# vibration_sensor.net
KiCad netlist of a schematic drawn in Altium Designer
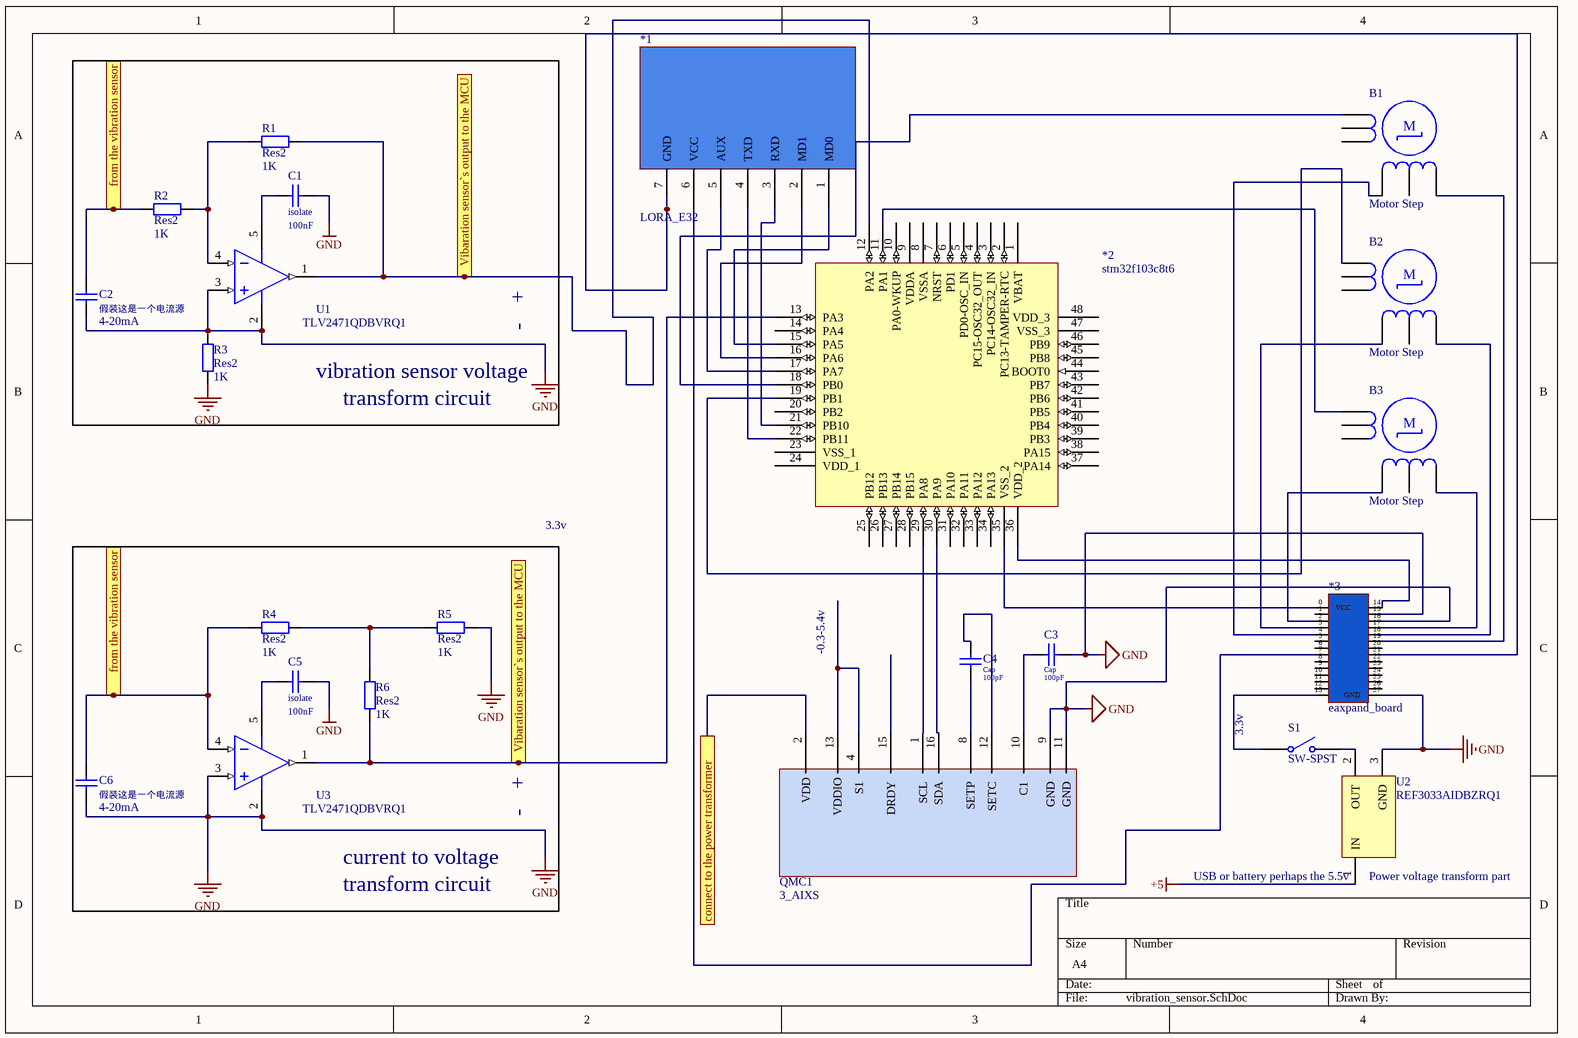
[diagram p0: vibration_sensor.SchDoc]

(export (version "E")
  (design (tool "Eeschema 10.0.6"))
  (components
    (comp (ref "*1")
      (value "LORA_E32")
      (footprint "LORA_AS62-T20")
      (description "EBYTE_USE_SEMTCH_CORE")
      (libsource (lib "lora") (part "LORA_E32"))
    )
    (comp (ref "*2") (value "stm32f103c8t6") (libsource (lib "stm32f103c8t6") (part "stm32f103c8t6")))
    (comp (ref "*3")
      (value "eaxpand_board")
      (footprint "expand_board")
      (libsource (lib "My_library") (part "eaxpand_board"))
    )
    (comp (ref "B1")
      (value "Motor Step")
      (footprint "DIP-6")
      (description "Motor Stepper")
      (fields (field (name "PUBLISHER") "Altium Limited"))
      (libsource (lib "Miscellaneous Devices") (part "Motor Step"))
    )
    (comp (ref "B2")
      (value "Motor Step")
      (footprint "DIP-6")
      (description "Motor Stepper")
      (fields (field (name "PUBLISHER") "Altium Limited"))
      (libsource (lib "Miscellaneous Devices") (part "Motor Step"))
    )
    (comp (ref "B3")
      (value "Motor Step")
      (footprint "DIP-6")
      (description "Motor Stepper")
      (fields (field (name "PUBLISHER") "Altium Limited"))
      (libsource (lib "Miscellaneous Devices") (part "Motor Step"))
    )
    (comp (ref "C1")
      (value "isolate")
      (footprint "RAD-0.3")
      (description "Capacitor")
      (fields (field (name "ALTIUM_VALUE") "100nF") (field (name "PUBLISHER") "Altium Limited"))
      (libsource (lib "Miscellaneous Devices") (part "Cap"))
    )
    (comp (ref "C2")
      (value "假装这是一个电流源")
      (footprint "RAD-0.3")
      (description "Capacitor")
      (fields (field (name "ALTIUM_VALUE") "4-20mA") (field (name "PUBLISHER") "Altium Limited"))
      (libsource (lib "Miscellaneous Devices") (part "Cap"))
    )
    (comp (ref "C3")
      (value "Cap")
      (footprint "RAD-0.3")
      (description "Capacitor")
      (fields (field (name "ALTIUM_VALUE") "100pF") (field (name "PUBLISHER") "Altium Limited"))
      (libsource (lib "Miscellaneous Devices") (part "Cap"))
    )
    (comp (ref "C4")
      (value "Cap")
      (footprint "RAD-0.3")
      (description "Capacitor")
      (fields (field (name "ALTIUM_VALUE") "100pF") (field (name "PUBLISHER") "Altium Limited"))
      (libsource (lib "Miscellaneous Devices") (part "Cap"))
    )
    (comp (ref "C5")
      (value "isolate")
      (footprint "RAD-0.3")
      (description "Capacitor")
      (fields (field (name "ALTIUM_VALUE") "100nF") (field (name "PUBLISHER") "Altium Limited"))
      (libsource (lib "Miscellaneous Devices") (part "Cap"))
    )
    (comp (ref "C6")
      (value "假装这是一个电流源")
      (footprint "RAD-0.3")
      (description "Capacitor")
      (fields (field (name "ALTIUM_VALUE") "4-20mA") (field (name "PUBLISHER") "Altium Limited"))
      (libsource (lib "Miscellaneous Devices") (part "Cap"))
    )
    (comp (ref "QMC1") (value "3_AIXS") (libsource (lib "QMC5883L") (part "QMC5883L")))
    (comp (ref "R1")
      (value "Res2")
      (footprint "AXIAL-0.4")
      (description "Resistor")
      (fields (field (name "ALTIUM_VALUE") "1K") (field (name "PUBLISHER") "Altium Limited"))
      (libsource (lib "") (part "Res2_2"))
    )
    (comp (ref "R2")
      (value "Res2")
      (footprint "AXIAL-0.4")
      (description "Resistor")
      (fields (field (name "ALTIUM_VALUE") "1K") (field (name "PUBLISHER") "Altium Limited"))
      (libsource (lib "Miscellaneous Devices") (part "Res2"))
    )
    (comp (ref "R3")
      (value "Res2")
      (footprint "AXIAL-0.4")
      (description "Resistor")
      (fields (field (name "ALTIUM_VALUE") "1K") (field (name "PUBLISHER") "Altium Limited"))
      (libsource (lib "") (part "Res2_1"))
    )
    (comp (ref "R4")
      (value "Res2")
      (footprint "AXIAL-0.4")
      (description "Resistor")
      (fields (field (name "ALTIUM_VALUE") "1K") (field (name "PUBLISHER") "Altium Limited"))
      (libsource (lib "") (part "Res2_2"))
    )
    (comp (ref "R5")
      (value "Res2")
      (footprint "AXIAL-0.4")
      (description "Resistor")
      (fields (field (name "ALTIUM_VALUE") "1K") (field (name "PUBLISHER") "Altium Limited"))
      (libsource (lib "Miscellaneous Devices") (part "Res2"))
    )
    (comp (ref "R6")
      (value "Res2")
      (footprint "AXIAL-0.4")
      (description "Resistor")
      (fields (field (name "ALTIUM_VALUE") "1K") (field (name "PUBLISHER") "Altium Limited"))
      (libsource (lib "") (part "Res2_1"))
    )
    (comp (ref "S1")
      (value "SW-SPST")
      (footprint "SPST-2")
      (description "Single-Pole, Single-Throw Switch")
      (fields (field (name "PUBLISHER") "Altium Limited"))
      (libsource (lib "Miscellaneous Devices") (part "SW-SPST"))
    )
    (comp (ref "U1")
      (value "TLV2471QDBVRQ1")
      (footprint "TI-DBV5_N")
      (fields (field (name "MANUFACTURER") "Texas Instruments"))
      (libsource (lib "TI Amplifiers and Linear Operational Amplifier Precision Amplifier Part Two") (part "TLV2471QDBVRQ1"))
    )
    (comp (ref "U2")
      (value "REF3033AIDBZRQ1")
      (footprint "TI-DBZ3_N")
      (fields (field (name "MANUFACTURER") "Texas Instruments"))
      (libsource (lib "TI Power Management Series Voltage Reference") (part "REF3033AIDBZRQ1"))
    )
    (comp (ref "U3")
      (value "TLV2471QDBVRQ1")
      (footprint "TI-DBV5_N")
      (fields (field (name "MANUFACTURER") "Texas Instruments"))
      (libsource (lib "TI Amplifiers and Linear Operational Amplifier Precision Amplifier Part Two") (part "TLV2471QDBVRQ1"))
    )
  )
  (nets
    (net (code "1") (name "+5") (class "Default")
      (node (ref "U2") (pin "1") (pinfunction "IN_1") (pintype "power_in"))
    )
    (net (code "2") (name "/Vibaration sensor`s output to the MCU") (class "Default")
      (node (ref "*2") (pin "12") (pinfunction "PA2_12") (pintype "bidirectional"))
      (node (ref "*2") (pin "13") (pinfunction "PA3_13") (pintype "bidirectional"))
      (node (ref "R1") (pin "1") (pinfunction "1_1") (pintype "passive"))
      (node (ref "R6") (pin "1") (pinfunction "1_1") (pintype "passive"))
      (node (ref "U1") (pin "1") (pinfunction "OUT_1") (pintype "output"))
      (node (ref "U3") (pin "1") (pinfunction "OUT_1") (pintype "output"))
    )
    (net (code "3") (name "/connect to the power transformer") (class "Default")
      (node (ref "QMC1") (pin "2") (pinfunction "VDD_2") (pintype "passive"))
    )
    (net (code "4") (name "/from the vibration sensor") (class "Default")
      (node (ref "C2") (pin "2") (pinfunction "2_2") (pintype "passive"))
      (node (ref "C6") (pin "2") (pinfunction "2_2") (pintype "passive"))
      (node (ref "R2") (pin "1") (pinfunction "1_1") (pintype "passive"))
      (node (ref "R4") (pin "2") (pinfunction "2_2") (pintype "passive"))
      (node (ref "U3") (pin "4") (pinfunction "IN-_4") (pintype "input"))
    )
    (net (code "5") (name "GND") (class "Default")
      (node (ref "*3") (pin "15") (pintype "power_in"))
      (node (ref "*3") (pin "16") (pintype "power_in"))
      (node (ref "*3") (pin "27") (pinfunction "GND_27") (pintype "power_in"))
      (node (ref "C1") (pin "1") (pinfunction "1_1") (pintype "passive"))
      (node (ref "C2") (pin "1") (pinfunction "1_1") (pintype "passive"))
      (node (ref "C3") (pin "1") (pinfunction "1_1") (pintype "passive"))
      (node (ref "C5") (pin "1") (pinfunction "1_1") (pintype "passive"))
      (node (ref "C6") (pin "1") (pinfunction "1_1") (pintype "passive"))
      (node (ref "QMC1") (pin "11") (pinfunction "GND_11") (pintype "passive"))
      (node (ref "QMC1") (pin "9") (pinfunction "GND_9") (pintype "passive"))
      (node (ref "R3") (pin "1") (pinfunction "1_1") (pintype "passive"))
      (node (ref "R3") (pin "2") (pinfunction "2_2") (pintype "passive"))
      (node (ref "R5") (pin "2") (pinfunction "2_2") (pintype "passive"))
      (node (ref "U1") (pin "2") (pinfunction "GND_2") (pintype "power_in"))
      (node (ref "U1") (pin "3") (pinfunction "IN+_3") (pintype "input"))
      (node (ref "U2") (pin "3") (pinfunction "GND_3") (pintype "power_in"))
      (node (ref "U3") (pin "2") (pinfunction "GND_2") (pintype "power_in"))
      (node (ref "U3") (pin "3") (pinfunction "IN+_3") (pintype "input"))
    )
    (net (code "6") (name "Net-(*1-AUX)") (class "Default")
      (node (ref "*1") (pin "5") (pinfunction "AUX_5") (pintype "passive"))
      (node (ref "*2") (pin "17") (pinfunction "PA7_17") (pintype "bidirectional"))
    )
    (net (code "7") (name "Net-(*1-GND)") (class "Default")
      (node (ref "*1") (pin "7") (pinfunction "GND_7") (pintype "passive"))
      (node (ref "*3") (pin "21") (pintype "power_in"))
    )
    (net (code "8") (name "Net-(*1-MD0)") (class "Default")
      (node (ref "*1") (pin "1") (pinfunction "MD0_1") (pintype "passive"))
      (node (ref "*2") (pin "15") (pinfunction "PA5_15") (pintype "bidirectional"))
    )
    (net (code "9") (name "Net-(*1-MD1)") (class "Default")
      (node (ref "*1") (pin "2") (pinfunction "MD1_2") (pintype "passive"))
      (node (ref "*2") (pin "16") (pinfunction "PA6_16") (pintype "bidirectional"))
    )
    (net (code "10") (name "Net-(*1-RXD)") (class "Default")
      (node (ref "*1") (pin "3") (pinfunction "RXD_3") (pintype "passive"))
      (node (ref "*2") (pin "21") (pinfunction "PB10_21") (pintype "bidirectional"))
    )
    (net (code "11") (name "Net-(*1-TXD)") (class "Default")
      (node (ref "*1") (pin "4") (pinfunction "TXD_4") (pintype "passive"))
      (node (ref "*2") (pin "22") (pinfunction "PB11_22") (pintype "bidirectional"))
    )
    (net (code "12") (name "Net-(*1-VCC)") (class "Default")
      (node (ref "*1") (pin "6") (pinfunction "VCC_6") (pintype "power_in"))
      (node (ref "*3") (pin "7") (pintype "power_in"))
    )
    (net (code "13") (name "Net-(*2-PA1)") (class "Default")
      (node (ref "*2") (pin "11") (pinfunction "PA1_11") (pintype "bidirectional"))
      (node (ref "B3") (pin "1") (pinfunction "1_1") (pintype "passive"))
    )
    (net (code "14") (name "Net-(*2-PA8)") (class "Default")
      (node (ref "*2") (pin "29") (pinfunction "PA8_29") (pintype "bidirectional"))
      (node (ref "QMC1") (pin "1") (pinfunction "SCL_1") (pintype "passive"))
    )
    (net (code "15") (name "Net-(*2-PA9)") (class "Default")
      (node (ref "*2") (pin "30") (pinfunction "PA9_30") (pintype "bidirectional"))
      (node (ref "QMC1") (pin "16") (pinfunction "SDA_16") (pintype "passive"))
    )
    (net (code "16") (name "Net-(*2-PB0)") (class "Default")
      (node (ref "*2") (pin "18") (pinfunction "PB0_18") (pintype "bidirectional"))
      (node (ref "B1") (pin "1") (pinfunction "1_1") (pintype "passive"))
    )
    (net (code "17") (name "Net-(*2-PB1)") (class "Default")
      (node (ref "*2") (pin "19") (pinfunction "PB1_19") (pintype "bidirectional"))
      (node (ref "B2") (pin "1") (pinfunction "1_1") (pintype "passive"))
    )
    (net (code "18") (name "Net-(*2-VDD_2)") (class "Default")
      (node (ref "*2") (pin "36") (pinfunction "VDD_2_36") (pintype "power_in"))
      (node (ref "*3") (pin "14") (pintype "power_in"))
    )
    (net (code "19") (name "Net-(*2-VSS_2)") (class "Default")
      (node (ref "*2") (pin "35") (pinfunction "VSS_2_35") (pintype "power_in"))
      (node (ref "*3") (pin "0") (pinfunction "VCC_0") (pintype "power_in"))
    )
    (net (code "20") (name "Net-(*3-Pad2)") (class "Default")
      (node (ref "*3") (pin "2") (pintype "power_in"))
      (node (ref "B3") (pin "4") (pinfunction "4_4") (pintype "passive"))
    )
    (net (code "21") (name "Net-(*3-Pad3)") (class "Default")
      (node (ref "*3") (pin "3") (pintype "power_in"))
      (node (ref "B2") (pin "4") (pinfunction "4_4") (pintype "passive"))
    )
    (net (code "22") (name "Net-(*3-Pad4)") (class "Default")
      (node (ref "*3") (pin "4") (pintype "power_in"))
      (node (ref "B1") (pin "4") (pinfunction "4_4") (pintype "passive"))
    )
    (net (code "23") (name "Net-(*3-Pad17)") (class "Default")
      (node (ref "*3") (pin "17") (pintype "power_in"))
      (node (ref "B3") (pin "6") (pinfunction "6_6") (pintype "passive"))
    )
    (net (code "24") (name "Net-(*3-Pad18)") (class "Default")
      (node (ref "*3") (pin "18") (pintype "power_in"))
      (node (ref "B2") (pin "6") (pinfunction "6_6") (pintype "passive"))
    )
    (net (code "25") (name "Net-(*3-Pad19)") (class "Default")
      (node (ref "*3") (pin "19") (pintype "power_in"))
      (node (ref "B1") (pin "6") (pinfunction "6_6") (pintype "passive"))
    )
    (net (code "26") (name "Net-(QMC1-C1)") (class "Default")
      (node (ref "C3") (pin "2") (pinfunction "2_2") (pintype "passive"))
      (node (ref "QMC1") (pin "10") (pinfunction "C1_10") (pintype "passive"))
    )
    (net (code "27") (name "Net-(QMC1-S1)") (class "Default")
      (node (ref "QMC1") (pin "13") (pinfunction "VDDIO_13") (pintype "passive"))
      (node (ref "QMC1") (pin "4") (pinfunction "S1_4") (pintype "passive"))
    )
    (net (code "28") (name "Net-(QMC1-SETC)") (class "Default")
      (node (ref "C4") (pin "2") (pinfunction "2_2") (pintype "passive"))
      (node (ref "QMC1") (pin "12") (pinfunction "SETC_12") (pintype "passive"))
    )
    (net (code "29") (name "Net-(QMC1-SETP)") (class "Default")
      (node (ref "C4") (pin "1") (pinfunction "1_1") (pintype "passive"))
      (node (ref "QMC1") (pin "8") (pinfunction "SETP_8") (pintype "passive"))
    )
    (net (code "30") (name "Net-(R4-Pad1)") (class "Default")
      (node (ref "R4") (pin "1") (pinfunction "1_1") (pintype "passive"))
      (node (ref "R5") (pin "1") (pinfunction "1_1") (pintype "passive"))
      (node (ref "R6") (pin "2") (pinfunction "2_2") (pintype "passive"))
    )
    (net (code "31") (name "Net-(S1-COMMON)") (class "Default")
      (node (ref "*3") (pin "13") (pintype "power_in"))
      (node (ref "S1") (pin "1") (pinfunction "COMMON_1") (pintype "passive"))
    )
    (net (code "32") (name "Net-(S1-NO)") (class "Default")
      (node (ref "S1") (pin "2") (pinfunction "NO_2") (pintype "passive"))
      (node (ref "U2") (pin "2") (pinfunction "OUT_2") (pintype "power_in"))
    )
    (net (code "33") (name "Net-(U1-IN-)") (class "Default")
      (node (ref "R1") (pin "2") (pinfunction "2_2") (pintype "passive"))
      (node (ref "R2") (pin "2") (pinfunction "2_2") (pintype "passive"))
      (node (ref "U1") (pin "4") (pinfunction "IN-_4") (pintype "input"))
    )
    (net (code "34") (name "Net-(U1-VDD)") (class "Default")
      (node (ref "C1") (pin "2") (pinfunction "2_2") (pintype "passive"))
      (node (ref "U1") (pin "5") (pinfunction "VDD_5") (pintype "power_in"))
    )
    (net (code "35") (name "Net-(U3-VDD)") (class "Default")
      (node (ref "C5") (pin "2") (pinfunction "2_2") (pintype "passive"))
      (node (ref "U3") (pin "5") (pinfunction "VDD_5") (pintype "power_in"))
    )
    (net (code "36") (name "unconnected-(*2-BOOT0-Pad44)") (class "Default")
      (node (ref "*2") (pin "44") (pinfunction "BOOT0_44") (pintype "input"))
    )
    (net (code "37") (name "unconnected-(*2-NRST-Pad7)") (class "Default")
      (node (ref "*2") (pin "7") (pinfunction "NRST_7") (pintype "bidirectional"))
    )
    (net (code "38") (name "unconnected-(*2-PA0-WKUP-Pad10)") (class "Default")
      (node (ref "*2") (pin "10") (pinfunction "PA0-WKUP_10") (pintype "bidirectional"))
    )
    (net (code "39") (name "unconnected-(*2-PA4-Pad14)") (class "Default")
      (node (ref "*2") (pin "14") (pinfunction "PA4_14") (pintype "bidirectional"))
    )
    (net (code "40") (name "unconnected-(*2-PA10-Pad31)") (class "Default")
      (node (ref "*2") (pin "31") (pinfunction "PA10_31") (pintype "bidirectional"))
    )
    (net (code "41") (name "unconnected-(*2-PA11-Pad32)") (class "Default")
      (node (ref "*2") (pin "32") (pinfunction "PA11_32") (pintype "bidirectional"))
    )
    (net (code "42") (name "unconnected-(*2-PA12-Pad33)") (class "Default")
      (node (ref "*2") (pin "33") (pinfunction "PA12_33") (pintype "bidirectional"))
    )
    (net (code "43") (name "unconnected-(*2-PA13-Pad34)") (class "Default")
      (node (ref "*2") (pin "34") (pinfunction "PA13_34") (pintype "bidirectional"))
    )
    (net (code "44") (name "unconnected-(*2-PA14-Pad37)") (class "Default")
      (node (ref "*2") (pin "37") (pinfunction "PA14_37") (pintype "bidirectional"))
    )
    (net (code "45") (name "unconnected-(*2-PA15-Pad38)") (class "Default")
      (node (ref "*2") (pin "38") (pinfunction "PA15_38") (pintype "bidirectional"))
    )
    (net (code "46") (name "unconnected-(*2-PB2-Pad20)") (class "Default")
      (node (ref "*2") (pin "20") (pinfunction "PB2_20") (pintype "bidirectional"))
    )
    (net (code "47") (name "unconnected-(*2-PB3-Pad39)") (class "Default")
      (node (ref "*2") (pin "39") (pinfunction "PB3_39") (pintype "bidirectional"))
    )
    (net (code "48") (name "unconnected-(*2-PB4-Pad40)") (class "Default")
      (node (ref "*2") (pin "40") (pinfunction "PB4_40") (pintype "bidirectional"))
    )
    (net (code "49") (name "unconnected-(*2-PB5-Pad41)") (class "Default")
      (node (ref "*2") (pin "41") (pinfunction "PB5_41") (pintype "bidirectional"))
    )
    (net (code "50") (name "unconnected-(*2-PB6-Pad42)") (class "Default")
      (node (ref "*2") (pin "42") (pinfunction "PB6_42") (pintype "bidirectional"))
    )
    (net (code "51") (name "unconnected-(*2-PB7-Pad43)") (class "Default")
      (node (ref "*2") (pin "43") (pinfunction "PB7_43") (pintype "bidirectional"))
    )
    (net (code "52") (name "unconnected-(*2-PB8-Pad45)") (class "Default")
      (node (ref "*2") (pin "45") (pinfunction "PB8_45") (pintype "bidirectional"))
    )
    (net (code "53") (name "unconnected-(*2-PB9-Pad46)") (class "Default")
      (node (ref "*2") (pin "46") (pinfunction "PB9_46") (pintype "bidirectional"))
    )
    (net (code "54") (name "unconnected-(*2-PB12-Pad25)") (class "Default")
      (node (ref "*2") (pin "25") (pinfunction "PB12_25") (pintype "bidirectional"))
    )
    (net (code "55") (name "unconnected-(*2-PB13-Pad26)") (class "Default")
      (node (ref "*2") (pin "26") (pinfunction "PB13_26") (pintype "bidirectional"))
    )
    (net (code "56") (name "unconnected-(*2-PB14-Pad27)") (class "Default")
      (node (ref "*2") (pin "27") (pinfunction "PB14_27") (pintype "bidirectional"))
    )
    (net (code "57") (name "unconnected-(*2-PB15-Pad28)") (class "Default")
      (node (ref "*2") (pin "28") (pinfunction "PB15_28") (pintype "bidirectional"))
    )
    (net (code "58") (name "unconnected-(*2-PC13-TAMPER-RTC-Pad2)") (class "Default")
      (node (ref "*2") (pin "2") (pinfunction "PC13-TAMPER-RTC_2") (pintype "bidirectional"))
    )
    (net (code "59") (name "unconnected-(*2-PC14-OSC32_IN-Pad3)") (class "Default")
      (node (ref "*2") (pin "3") (pinfunction "PC14-OSC32_IN_3") (pintype "bidirectional"))
    )
    (net (code "60") (name "unconnected-(*2-PC15-OSC32_OUT-Pad4)") (class "Default")
      (node (ref "*2") (pin "4") (pinfunction "PC15-OSC32_OUT_4") (pintype "bidirectional"))
    )
    (net (code "61") (name "unconnected-(*2-PD0-OSC_IN-Pad5)") (class "Default")
      (node (ref "*2") (pin "5") (pinfunction "PD0-OSC_IN_5") (pintype "bidirectional"))
    )
    (net (code "62") (name "unconnected-(*2-PD1-Pad6)") (class "Default")
      (node (ref "*2") (pin "6") (pinfunction "PD1_6") (pintype "bidirectional"))
    )
    (net (code "63") (name "unconnected-(*2-VBAT-Pad1)") (class "Default")
      (node (ref "*2") (pin "1") (pinfunction "VBAT_1") (pintype "power_in"))
    )
    (net (code "64") (name "unconnected-(*2-VDDA-Pad9)") (class "Default")
      (node (ref "*2") (pin "9") (pinfunction "VDDA_9") (pintype "power_in"))
    )
    (net (code "65") (name "unconnected-(*2-VDD_1-Pad24)") (class "Default")
      (node (ref "*2") (pin "24") (pinfunction "VDD_1_24") (pintype "power_in"))
    )
    (net (code "66") (name "unconnected-(*2-VDD_3-Pad48)") (class "Default")
      (node (ref "*2") (pin "48") (pinfunction "VDD_3_48") (pintype "power_in"))
    )
    (net (code "67") (name "unconnected-(*2-VSSA-Pad8)") (class "Default")
      (node (ref "*2") (pin "8") (pinfunction "VSSA_8") (pintype "power_in"))
    )
    (net (code "68") (name "unconnected-(*2-VSS_1-Pad23)") (class "Default")
      (node (ref "*2") (pin "23") (pinfunction "VSS_1_23") (pintype "power_in"))
    )
    (net (code "69") (name "unconnected-(*2-VSS_3-Pad47)") (class "Default")
      (node (ref "*2") (pin "47") (pinfunction "VSS_3_47") (pintype "power_in"))
    )
    (net (code "70") (name "unconnected-(*3-Pad1)") (class "Default")
      (node (ref "*3") (pin "1") (pintype "power_in"))
    )
    (net (code "71") (name "unconnected-(*3-Pad5)") (class "Default")
      (node (ref "*3") (pin "5") (pintype "power_in"))
    )
    (net (code "72") (name "unconnected-(*3-Pad6)") (class "Default")
      (node (ref "*3") (pin "6") (pintype "power_in"))
    )
    (net (code "73") (name "unconnected-(*3-Pad8)") (class "Default")
      (node (ref "*3") (pin "8") (pintype "power_in"))
    )
    (net (code "74") (name "unconnected-(*3-Pad9)") (class "Default")
      (node (ref "*3") (pin "9") (pintype "power_in"))
    )
    (net (code "75") (name "unconnected-(*3-Pad10)") (class "Default")
      (node (ref "*3") (pin "10") (pintype "power_in"))
    )
    (net (code "76") (name "unconnected-(*3-Pad11)") (class "Default")
      (node (ref "*3") (pin "11") (pintype "power_in"))
    )
    (net (code "77") (name "unconnected-(*3-Pad12)") (class "Default")
      (node (ref "*3") (pin "12") (pintype "power_in"))
    )
    (net (code "78") (name "unconnected-(*3-Pad20)") (class "Default")
      (node (ref "*3") (pin "20") (pintype "power_in"))
    )
    (net (code "79") (name "unconnected-(*3-Pad22)") (class "Default")
      (node (ref "*3") (pin "22") (pintype "power_in"))
    )
    (net (code "80") (name "unconnected-(*3-Pad23)") (class "Default")
      (node (ref "*3") (pin "23") (pintype "power_in"))
    )
    (net (code "81") (name "unconnected-(*3-Pad24)") (class "Default")
      (node (ref "*3") (pin "24") (pintype "power_in"))
    )
    (net (code "82") (name "unconnected-(*3-Pad25)") (class "Default")
      (node (ref "*3") (pin "25") (pintype "power_in"))
    )
    (net (code "83") (name "unconnected-(*3-Pad26)") (class "Default")
      (node (ref "*3") (pin "26") (pintype "power_in"))
    )
    (net (code "84") (name "unconnected-(B1-Pad2)") (class "Default")
      (node (ref "B1") (pin "2") (pinfunction "2_2") (pintype "passive"))
    )
    (net (code "85") (name "unconnected-(B1-Pad3)") (class "Default")
      (node (ref "B1") (pin "3") (pinfunction "3_3") (pintype "passive"))
    )
    (net (code "86") (name "unconnected-(B1-Pad5)") (class "Default")
      (node (ref "B1") (pin "5") (pinfunction "5_5") (pintype "passive"))
    )
    (net (code "87") (name "unconnected-(B2-Pad2)") (class "Default")
      (node (ref "B2") (pin "2") (pinfunction "2_2") (pintype "passive"))
    )
    (net (code "88") (name "unconnected-(B2-Pad3)") (class "Default")
      (node (ref "B2") (pin "3") (pinfunction "3_3") (pintype "passive"))
    )
    (net (code "89") (name "unconnected-(B2-Pad5)") (class "Default")
      (node (ref "B2") (pin "5") (pinfunction "5_5") (pintype "passive"))
    )
    (net (code "90") (name "unconnected-(B3-Pad2)") (class "Default")
      (node (ref "B3") (pin "2") (pinfunction "2_2") (pintype "passive"))
    )
    (net (code "91") (name "unconnected-(B3-Pad3)") (class "Default")
      (node (ref "B3") (pin "3") (pinfunction "3_3") (pintype "passive"))
    )
    (net (code "92") (name "unconnected-(B3-Pad5)") (class "Default")
      (node (ref "B3") (pin "5") (pinfunction "5_5") (pintype "passive"))
    )
    (net (code "93") (name "unconnected-(QMC1-DRDY-Pad15)") (class "Default")
      (node (ref "QMC1") (pin "15") (pinfunction "DRDY_15") (pintype "passive"))
    )
  )
)
